# Sheet1.net
KiCad netlist of a schematic drawn in Altium Designer
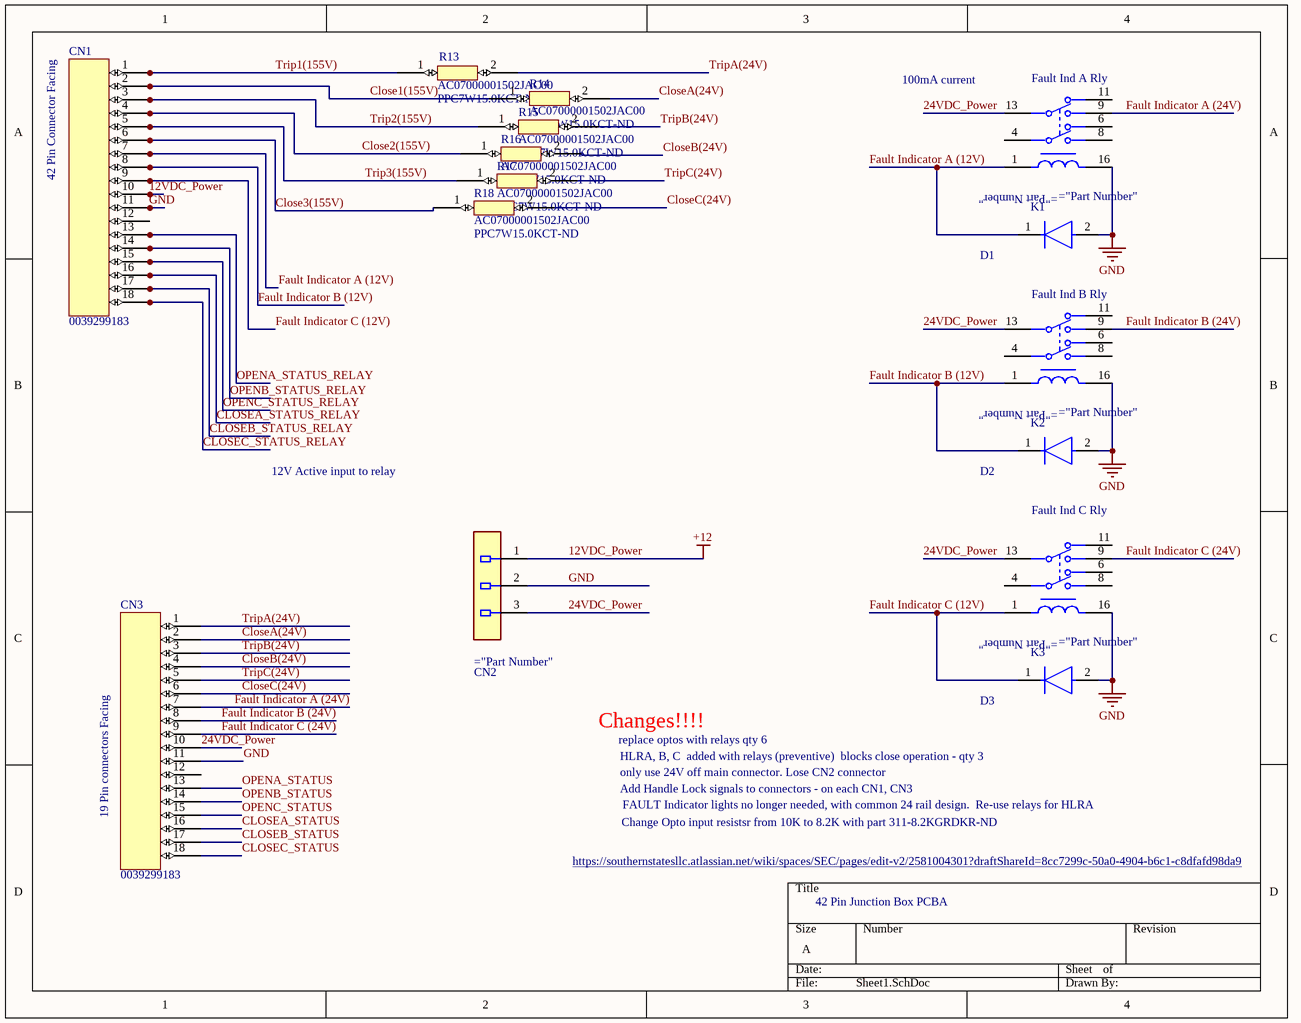
[diagram p0: Sheet1.SchDoc]

(export (version "E")
  (design (tool "Eeschema 10.0.6"))
  (components
    (comp (ref "CN1")
      (value "0039299183")
      (footprint "0039299183")
      (description "Connector Header Through Hole 18 position 0.165\" (4.20mm)")
      (libsource (lib "42PinJunctionBox") (part "0039299183 - 18 pin molex mini fit jr 5566"))
    )
    (comp (ref "CN2")
      (value "15-31-1036")
      (footprint "Molex_15-31-1036_0")
      (libsource (lib "ASD_MASTER") (part "15-31-1036"))
    )
    (comp (ref "CN3")
      (value "0039299183")
      (footprint "0039299183")
      (description "Connector Header Through Hole 18 position 0.165\" (4.20mm)")
      (libsource (lib "42PinJunctionBox") (part "0039299183 - 18 pin molex mini fit jr 5566"))
    )
    (comp (ref "D1")
      (value "S1A-13-F")
      (footprint "Micro_Commercial_DO-214AC_MFG")
      (libsource (lib "Diode_Micro_Commercial_FM2000GP_eec") (part "FM2000GP"))
    )
    (comp (ref "D2")
      (value "S1A-13-F")
      (footprint "Micro_Commercial_DO-214AC_MFG")
      (libsource (lib "Diode_Micro_Commercial_FM2000GP_eec") (part "FM2000GP"))
    )
    (comp (ref "D3")
      (value "S1A-13-F")
      (footprint "Micro_Commercial_DO-214AC_MFG")
      (libsource (lib "Diode_Micro_Commercial_FM2000GP_eec") (part "FM2000GP"))
    )
    (comp (ref "K1")
      (value "DS2Y-S-DC24V")
      (footprint "Panasonic_DS2Y-S-DC24V_0")
      (libsource (lib "ASD_MASTER") (part "DS2Y-S-DC24V"))
    )
    (comp (ref "K2")
      (value "DS2Y-S-DC24V")
      (footprint "Panasonic_DS2Y-S-DC24V_0")
      (libsource (lib "ASD_MASTER") (part "DS2Y-S-DC24V"))
    )
    (comp (ref "K3")
      (value "DS2Y-S-DC24V")
      (footprint "Panasonic_DS2Y-S-DC24V_0")
      (libsource (lib "ASD_MASTER") (part "DS2Y-S-DC24V"))
    )
    (comp (ref "R13")
      (value "AC07000001502JAC00")
      (footprint "AC07000001502JAC00")
      (fields
        (field (name "MANUFACTURER") "Vishay BCcomponents")
        (field (name "TOLERANCE") "5%")
        (field (name "SUPPLIER PART NUMBER 1") "PPC7W15.0KCT-ND")
      )
      (libsource (lib "42PinJunctionBox") (part "AC07000001502JAC00"))
    )
    (comp (ref "R14")
      (value "AC07000001502JAC00")
      (footprint "AC07000001502JAC00")
      (fields
        (field (name "MANUFACTURER") "Vishay BCcomponents")
        (field (name "TOLERANCE") "5%")
        (field (name "SUPPLIER PART NUMBER 1") "PPC7W15.0KCT-ND")
      )
      (libsource (lib "42PinJunctionBox") (part "AC07000001502JAC00"))
    )
    (comp (ref "R15")
      (value "AC07000001502JAC00")
      (footprint "AC07000001502JAC00")
      (fields
        (field (name "MANUFACTURER") "Vishay BCcomponents")
        (field (name "TOLERANCE") "5%")
        (field (name "SUPPLIER PART NUMBER 1") "PPC7W15.0KCT-ND")
      )
      (libsource (lib "42PinJunctionBox") (part "AC07000001502JAC00"))
    )
    (comp (ref "R16")
      (value "AC07000001502JAC00")
      (footprint "AC07000001502JAC00")
      (fields
        (field (name "MANUFACTURER") "Vishay BCcomponents")
        (field (name "TOLERANCE") "5%")
        (field (name "SUPPLIER PART NUMBER 1") "PPC7W15.0KCT-ND")
      )
      (libsource (lib "42PinJunctionBox") (part "AC07000001502JAC00"))
    )
    (comp (ref "R17")
      (value "AC07000001502JAC00")
      (footprint "AC07000001502JAC00")
      (fields
        (field (name "MANUFACTURER") "Vishay BCcomponents")
        (field (name "TOLERANCE") "5%")
        (field (name "SUPPLIER PART NUMBER 1") "PPC7W15.0KCT-ND")
      )
      (libsource (lib "42PinJunctionBox") (part "AC07000001502JAC00"))
    )
    (comp (ref "R18")
      (value "AC07000001502JAC00")
      (footprint "AC07000001502JAC00")
      (fields
        (field (name "MANUFACTURER") "Vishay BCcomponents")
        (field (name "TOLERANCE") "5%")
        (field (name "SUPPLIER PART NUMBER 1") "PPC7W15.0KCT-ND")
      )
      (libsource (lib "42PinJunctionBox") (part "AC07000001502JAC00"))
    )
  )
  (nets
    (net (code "1") (name "+12") (class "Default")
      (node (ref "CN1") (pin "10") (pintype "bidirectional"))
      (node (ref "CN2") (pin "1") (pinfunction "1_1") (pintype "passive"))
    )
    (net (code "2") (name "/24VDC_Power") (class "Default")
      (node (ref "CN2") (pin "3") (pinfunction "3_3") (pintype "passive"))
      (node (ref "CN3") (pin "10") (pintype "bidirectional"))
      (node (ref "K1") (pin "13") (pinfunction "2_COM_13") (pintype "passive"))
      (node (ref "K2") (pin "13") (pinfunction "2_COM_13") (pintype "passive"))
      (node (ref "K3") (pin "13") (pinfunction "2_COM_13") (pintype "passive"))
    )
    (net (code "3") (name "/CLOSEA_STATUS") (class "Default")
      (node (ref "CN3") (pin "16") (pintype "bidirectional"))
    )
    (net (code "4") (name "/CLOSEA_STATUS_RELAY") (class "Default")
      (node (ref "CN1") (pin "16") (pintype "bidirectional"))
    )
    (net (code "5") (name "/CLOSEB_STATUS") (class "Default")
      (node (ref "CN3") (pin "17") (pintype "bidirectional"))
    )
    (net (code "6") (name "/CLOSEB_STATUS_RELAY") (class "Default")
      (node (ref "CN1") (pin "17") (pintype "bidirectional"))
    )
    (net (code "7") (name "/CLOSEC_STATUS") (class "Default")
      (node (ref "CN3") (pin "18") (pintype "bidirectional"))
    )
    (net (code "8") (name "/CLOSEC_STATUS_RELAY") (class "Default")
      (node (ref "CN1") (pin "18") (pintype "bidirectional"))
    )
    (net (code "9") (name "/Close1(155V)") (class "Default")
      (node (ref "CN1") (pin "2") (pintype "bidirectional"))
      (node (ref "R14") (pin "1") (pintype "bidirectional"))
    )
    (net (code "10") (name "/Close2(155V)") (class "Default")
      (node (ref "CN1") (pin "4") (pintype "bidirectional"))
      (node (ref "R16") (pin "1") (pintype "bidirectional"))
    )
    (net (code "11") (name "/Close3(155V)") (class "Default")
      (node (ref "CN1") (pin "6") (pintype "bidirectional"))
      (node (ref "R18") (pin "1") (pintype "bidirectional"))
    )
    (net (code "12") (name "/CloseA(24V)") (class "Default")
      (node (ref "CN3") (pin "2") (pintype "bidirectional"))
      (node (ref "R14") (pin "2") (pintype "bidirectional"))
    )
    (net (code "13") (name "/CloseB(24V)") (class "Default")
      (node (ref "CN3") (pin "4") (pintype "bidirectional"))
      (node (ref "R16") (pin "2") (pintype "bidirectional"))
    )
    (net (code "14") (name "/CloseC(24V)") (class "Default")
      (node (ref "CN3") (pin "6") (pintype "bidirectional"))
      (node (ref "R18") (pin "2") (pintype "bidirectional"))
    )
    (net (code "15") (name "/Fault Indicator A (12V)") (class "Default")
      (node (ref "CN1") (pin "7") (pintype "bidirectional"))
      (node (ref "D1") (pin "1") (pinfunction "C_1") (pintype "passive"))
      (node (ref "K1") (pin "1") (pinfunction "+_1") (pintype "passive"))
    )
    (net (code "16") (name "/Fault Indicator A (24V)") (class "Default")
      (node (ref "CN3") (pin "7") (pintype "bidirectional"))
      (node (ref "K1") (pin "9") (pinfunction "2_N.O._9") (pintype "passive"))
    )
    (net (code "17") (name "/Fault Indicator B (12V)") (class "Default")
      (node (ref "CN1") (pin "8") (pintype "bidirectional"))
      (node (ref "D2") (pin "1") (pinfunction "C_1") (pintype "passive"))
      (node (ref "K2") (pin "1") (pinfunction "+_1") (pintype "passive"))
    )
    (net (code "18") (name "/Fault Indicator B (24V)") (class "Default")
      (node (ref "CN3") (pin "8") (pintype "bidirectional"))
      (node (ref "K2") (pin "9") (pinfunction "2_N.O._9") (pintype "passive"))
    )
    (net (code "19") (name "/Fault Indicator C (12V)") (class "Default")
      (node (ref "CN1") (pin "9") (pintype "bidirectional"))
      (node (ref "D3") (pin "1") (pinfunction "C_1") (pintype "passive"))
      (node (ref "K3") (pin "1") (pinfunction "+_1") (pintype "passive"))
    )
    (net (code "20") (name "/Fault Indicator C (24V)") (class "Default")
      (node (ref "CN3") (pin "9") (pintype "bidirectional"))
      (node (ref "K3") (pin "9") (pinfunction "2_N.O._9") (pintype "passive"))
    )
    (net (code "21") (name "/OPENA_STATUS") (class "Default")
      (node (ref "CN3") (pin "13") (pintype "bidirectional"))
    )
    (net (code "22") (name "/OPENA_STATUS_RELAY") (class "Default")
      (node (ref "CN1") (pin "13") (pintype "bidirectional"))
    )
    (net (code "23") (name "/OPENB_STATUS") (class "Default")
      (node (ref "CN3") (pin "14") (pintype "bidirectional"))
    )
    (net (code "24") (name "/OPENB_STATUS_RELAY") (class "Default")
      (node (ref "CN1") (pin "14") (pintype "bidirectional"))
    )
    (net (code "25") (name "/OPENC_STATUS") (class "Default")
      (node (ref "CN3") (pin "15") (pintype "bidirectional"))
    )
    (net (code "26") (name "/OPENC_STATUS_RELAY") (class "Default")
      (node (ref "CN1") (pin "15") (pintype "bidirectional"))
    )
    (net (code "27") (name "/Trip1(155V)") (class "Default")
      (node (ref "CN1") (pin "1") (pintype "bidirectional"))
      (node (ref "R13") (pin "1") (pintype "bidirectional"))
    )
    (net (code "28") (name "/Trip2(155V)") (class "Default")
      (node (ref "CN1") (pin "3") (pintype "bidirectional"))
      (node (ref "R15") (pin "1") (pintype "bidirectional"))
    )
    (net (code "29") (name "/Trip3(155V)") (class "Default")
      (node (ref "CN1") (pin "5") (pintype "bidirectional"))
      (node (ref "R17") (pin "1") (pintype "bidirectional"))
    )
    (net (code "30") (name "/TripA(24V)") (class "Default")
      (node (ref "CN3") (pin "1") (pintype "bidirectional"))
      (node (ref "R13") (pin "2") (pintype "bidirectional"))
    )
    (net (code "31") (name "/TripB(24V)") (class "Default")
      (node (ref "CN3") (pin "3") (pintype "bidirectional"))
      (node (ref "R15") (pin "2") (pintype "bidirectional"))
    )
    (net (code "32") (name "/TripC(24V)") (class "Default")
      (node (ref "CN3") (pin "5") (pintype "bidirectional"))
      (node (ref "R17") (pin "2") (pintype "bidirectional"))
    )
    (net (code "33") (name "GND") (class "Default")
      (node (ref "CN1") (pin "11") (pintype "bidirectional"))
      (node (ref "CN2") (pin "2") (pinfunction "2_2") (pintype "passive"))
      (node (ref "CN3") (pin "11") (pintype "bidirectional"))
      (node (ref "D1") (pin "2") (pinfunction "A_2") (pintype "passive"))
      (node (ref "D2") (pin "2") (pinfunction "A_2") (pintype "passive"))
      (node (ref "D3") (pin "2") (pinfunction "A_2") (pintype "passive"))
      (node (ref "K1") (pin "16") (pinfunction "-_16") (pintype "passive"))
      (node (ref "K2") (pin "16") (pinfunction "-_16") (pintype "passive"))
      (node (ref "K3") (pin "16") (pinfunction "-_16") (pintype "passive"))
    )
    (net (code "34") (name "unconnected-(CN1-Pad12)") (class "Default")
      (node (ref "CN1") (pin "12") (pintype "bidirectional"))
    )
    (net (code "35") (name "unconnected-(CN3-Pad12)") (class "Default")
      (node (ref "CN3") (pin "12") (pintype "bidirectional"))
    )
    (net (code "36") (name "unconnected-(K1-1_COM-Pad4)") (class "Default")
      (node (ref "K1") (pin "4") (pinfunction "1_COM_4") (pintype "passive"))
    )
    (net (code "37") (name "unconnected-(K1-1_N.C.-Pad6)") (class "Default")
      (node (ref "K1") (pin "6") (pinfunction "1_N.C._6") (pintype "passive"))
    )
    (net (code "38") (name "unconnected-(K1-1_N.O.-Pad8)") (class "Default")
      (node (ref "K1") (pin "8") (pinfunction "1_N.O._8") (pintype "passive"))
    )
    (net (code "39") (name "unconnected-(K1-2_N.C.-Pad11)") (class "Default")
      (node (ref "K1") (pin "11") (pinfunction "2_N.C._11") (pintype "passive"))
    )
    (net (code "40") (name "unconnected-(K2-1_COM-Pad4)") (class "Default")
      (node (ref "K2") (pin "4") (pinfunction "1_COM_4") (pintype "passive"))
    )
    (net (code "41") (name "unconnected-(K2-1_N.C.-Pad6)") (class "Default")
      (node (ref "K2") (pin "6") (pinfunction "1_N.C._6") (pintype "passive"))
    )
    (net (code "42") (name "unconnected-(K2-1_N.O.-Pad8)") (class "Default")
      (node (ref "K2") (pin "8") (pinfunction "1_N.O._8") (pintype "passive"))
    )
    (net (code "43") (name "unconnected-(K2-2_N.C.-Pad11)") (class "Default")
      (node (ref "K2") (pin "11") (pinfunction "2_N.C._11") (pintype "passive"))
    )
    (net (code "44") (name "unconnected-(K3-1_COM-Pad4)") (class "Default")
      (node (ref "K3") (pin "4") (pinfunction "1_COM_4") (pintype "passive"))
    )
    (net (code "45") (name "unconnected-(K3-1_N.C.-Pad6)") (class "Default")
      (node (ref "K3") (pin "6") (pinfunction "1_N.C._6") (pintype "passive"))
    )
    (net (code "46") (name "unconnected-(K3-1_N.O.-Pad8)") (class "Default")
      (node (ref "K3") (pin "8") (pinfunction "1_N.O._8") (pintype "passive"))
    )
    (net (code "47") (name "unconnected-(K3-2_N.C.-Pad11)") (class "Default")
      (node (ref "K3") (pin "11") (pinfunction "2_N.C._11") (pintype "passive"))
    )
  )
)
